# mini_controller_m328.net
KiCad netlist of a schematic drawn in EAGLE
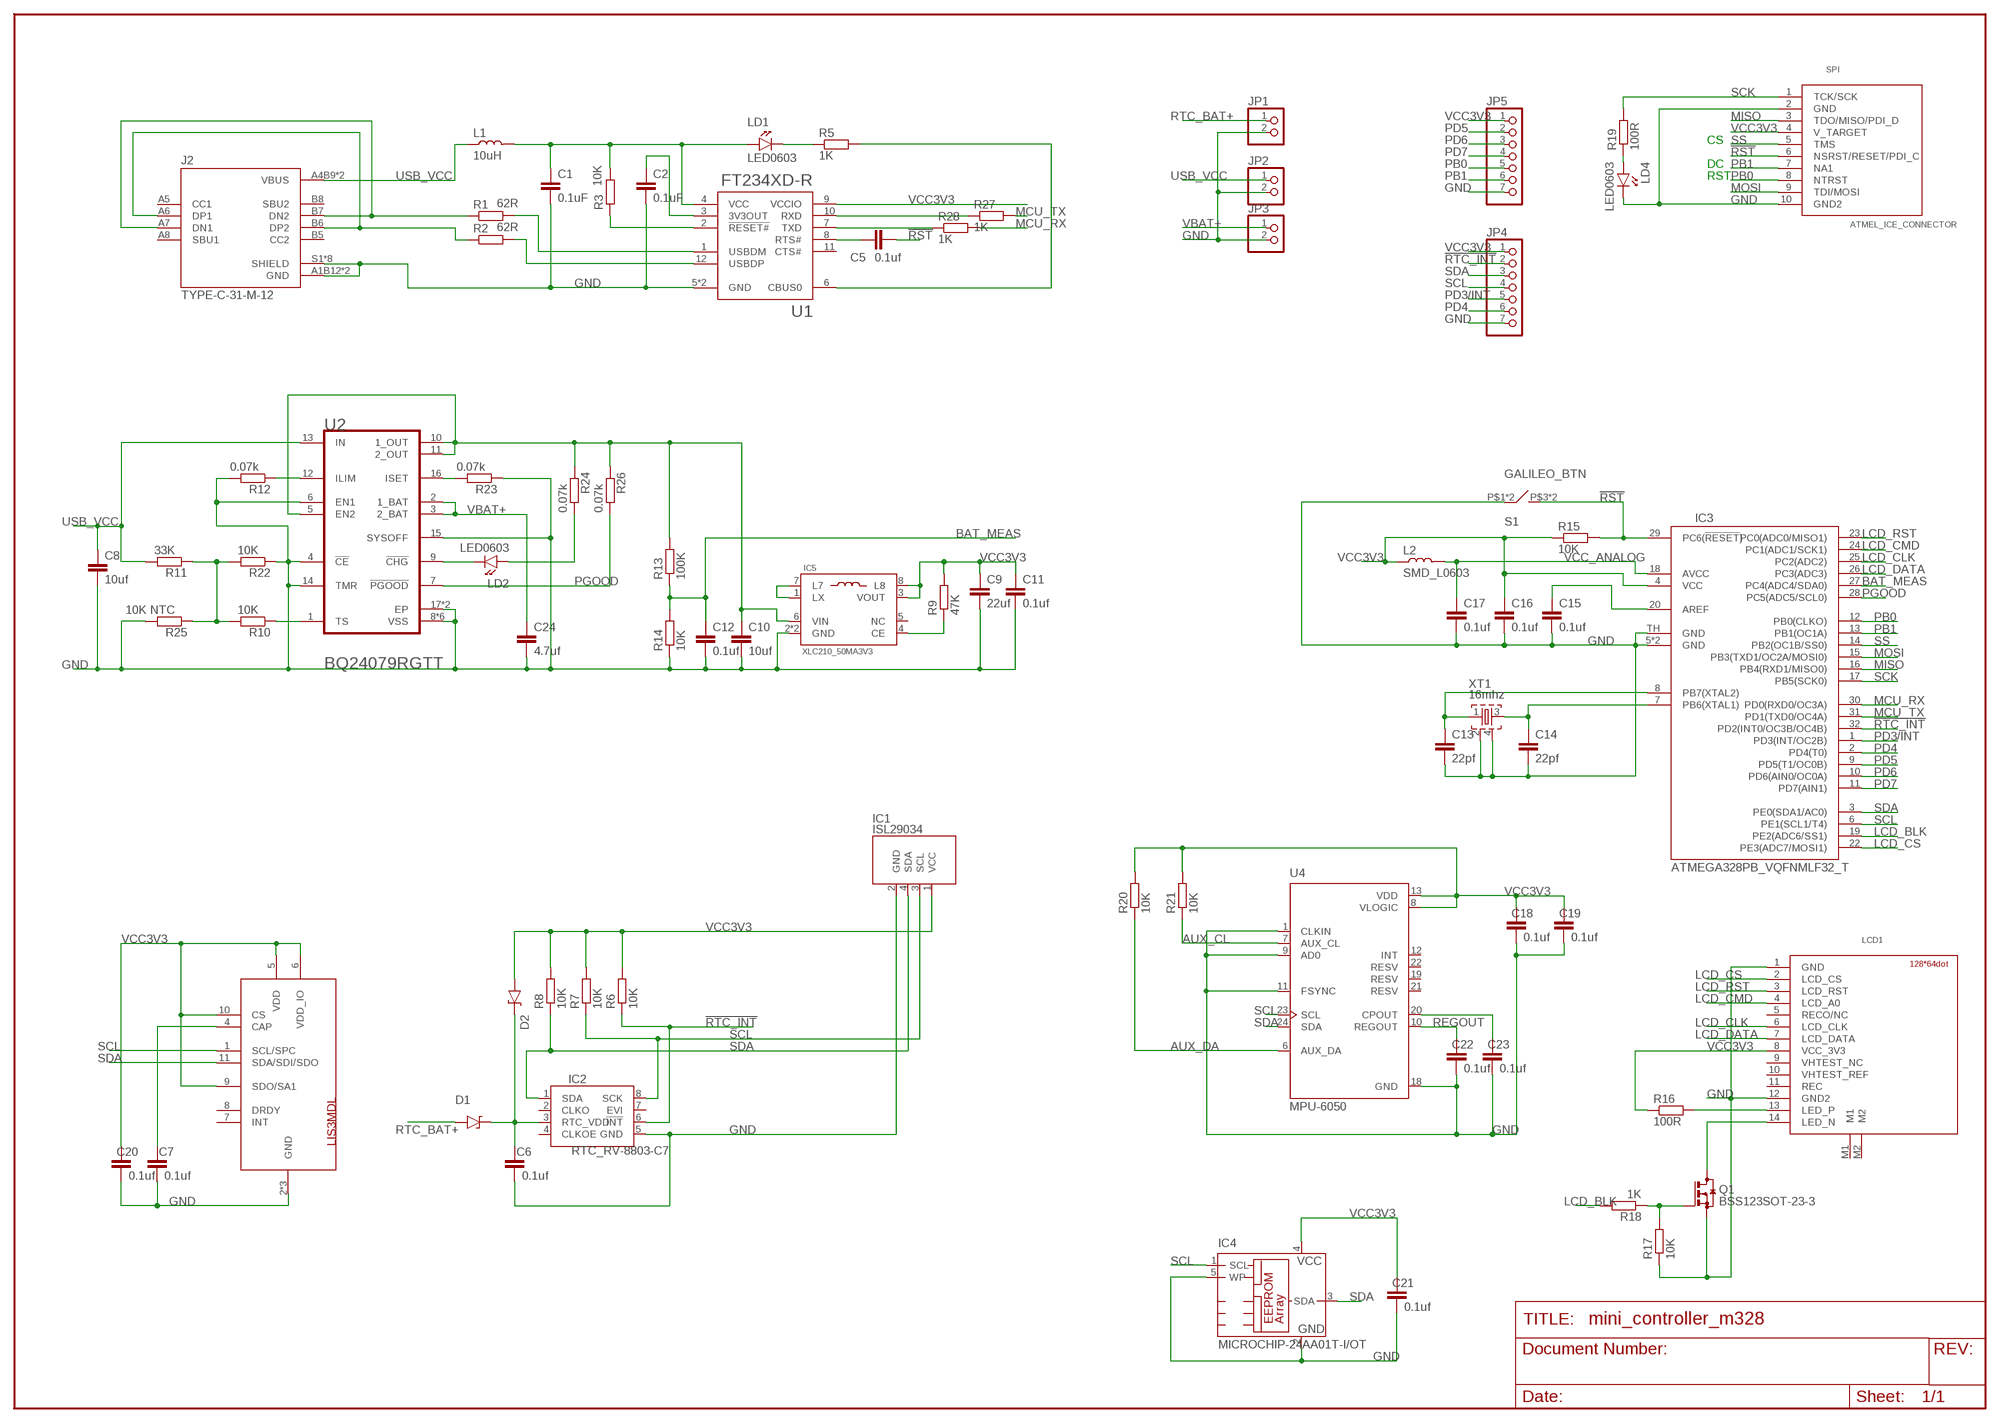
[diagram p0: schematic, sheet 1]

(export (version "E")
  (design (tool "Eeschema 10.0.6"))
  (components
    (comp (ref "C1")
      (value "0.1uF")
      (footprint "eagle-import:0603")
      (libsource (lib "eagle-import") (part "SMD_C0603"))
    )
    (comp (ref "C2")
      (value "0.1uF")
      (footprint "eagle-import:0603")
      (libsource (lib "eagle-import") (part "SMD_C0603"))
    )
    (comp (ref "C5")
      (value "0.1uf")
      (footprint "eagle-import:0603")
      (libsource (lib "eagle-import") (part "SMD_C0603"))
    )
    (comp (ref "C6")
      (value "0.1uf")
      (footprint "eagle-import:0603")
      (libsource (lib "eagle-import") (part "SMD_C0603"))
    )
    (comp (ref "C7")
      (value "0.1uf")
      (footprint "eagle-import:0603")
      (libsource (lib "eagle-import") (part "SMD_C0603"))
    )
    (comp (ref "C8")
      (value "10uf")
      (footprint "eagle-import:1206")
      (libsource (lib "eagle-import") (part "SMD_C1206"))
    )
    (comp (ref "C9")
      (value "22uf")
      (footprint "eagle-import:0805")
      (libsource (lib "eagle-import") (part "SMD_C0805"))
    )
    (comp (ref "C10")
      (value "10uf")
      (footprint "eagle-import:0603")
      (libsource (lib "eagle-import") (part "SMD_C0603"))
    )
    (comp (ref "C11")
      (value "0.1uf")
      (footprint "eagle-import:0603")
      (libsource (lib "eagle-import") (part "SMD_C0603"))
    )
    (comp (ref "C12")
      (value "0.1uf")
      (footprint "eagle-import:0603")
      (libsource (lib "eagle-import") (part "SMD_C0603"))
    )
    (comp (ref "C13")
      (value "22pf")
      (footprint "eagle-import:0603")
      (libsource (lib "eagle-import") (part "SMD_C0603"))
    )
    (comp (ref "C14")
      (value "22pf")
      (footprint "eagle-import:0603")
      (libsource (lib "eagle-import") (part "SMD_C0603"))
    )
    (comp (ref "C15")
      (value "0.1uf")
      (footprint "eagle-import:0603")
      (libsource (lib "eagle-import") (part "SMD_C0603"))
    )
    (comp (ref "C16")
      (value "0.1uf")
      (footprint "eagle-import:0603")
      (libsource (lib "eagle-import") (part "SMD_C0603"))
    )
    (comp (ref "C17")
      (value "0.1uf")
      (footprint "eagle-import:0603")
      (libsource (lib "eagle-import") (part "SMD_C0603"))
    )
    (comp (ref "C18")
      (value "0.1uf")
      (footprint "eagle-import:0603")
      (libsource (lib "eagle-import") (part "SMD_C0603"))
    )
    (comp (ref "C19")
      (value "0.1uf")
      (footprint "eagle-import:0603")
      (libsource (lib "eagle-import") (part "SMD_C0603"))
    )
    (comp (ref "C20")
      (value "0.1uf")
      (footprint "eagle-import:0603")
      (libsource (lib "eagle-import") (part "SMD_C0603"))
    )
    (comp (ref "C21")
      (value "0.1uf")
      (footprint "eagle-import:0603")
      (libsource (lib "eagle-import") (part "SMD_C0603"))
    )
    (comp (ref "C22")
      (value "0.1uf")
      (footprint "eagle-import:0603")
      (libsource (lib "eagle-import") (part "SMD_C0603"))
    )
    (comp (ref "C23")
      (value "0.1uf")
      (footprint "eagle-import:0603")
      (libsource (lib "eagle-import") (part "SMD_C0603"))
    )
    (comp (ref "C24")
      (value "4.7uf")
      (footprint "eagle-import:0805")
      (libsource (lib "eagle-import") (part "SMD_C0805"))
    )
    (comp (ref "D1")
      (value "D_SOD323")
      (footprint "eagle-import:SOD-323_D")
      (libsource (lib "eagle-import") (part "D_SOD323"))
    )
    (comp (ref "D2")
      (value "D_SOD323")
      (footprint "eagle-import:SOD-323_D")
      (libsource (lib "eagle-import") (part "D_SOD323"))
    )
    (comp (ref "IC1")
      (value "ISL29034")
      (footprint "eagle-import:ISL29034")
      (libsource (lib "eagle-import") (part "ISL29034"))
    )
    (comp (ref "IC2")
      (value "RTC_RV-8803-C7")
      (footprint "eagle-import:C7_RTC")
      (libsource (lib "eagle-import") (part "RTC_RV-8803-C7"))
    )
    (comp (ref "IC3")
      (value "ATMEGA328PB_VQFNMLF32_T")
      (footprint "eagle-import:MLF32-TH")
      (libsource (lib "eagle-import") (part "ATMEGA328PB_VQFNMLF32_T"))
    )
    (comp (ref "IC4")
      (value "MICROCHIP-24AA01T-I/OT")
      (footprint "eagle-import:SOT-23(5)")
      (libsource (lib "eagle-import") (part "MICROCHIP-24AA01T-I/OT"))
    )
    (comp (ref "IC5")
      (value "XLC210_50MA3V3")
      (footprint "eagle-import:XCL210_50MA3V3")
      (libsource (lib "eagle-import") (part "XLC210_50MA3V3"))
    )
    (comp (ref "J2")
      (value "TYPE-C-31-M-12")
      (footprint "eagle-import:HRO_TYPE-C-31-M-12")
      (fields (field (name "MF") "HRO Electronics Co., Ltd."))
      (libsource (lib "eagle-import") (part "TYPE-C-31-M-12"))
    )
    (comp (ref "JP1")
      (value "PINHD-1X2")
      (footprint "eagle-import:1X02")
      (libsource (lib "eagle-import") (part "PINHD-1X2"))
    )
    (comp (ref "JP2")
      (value "PINHD-1X2")
      (footprint "eagle-import:1X02")
      (libsource (lib "eagle-import") (part "PINHD-1X2"))
    )
    (comp (ref "JP3")
      (value "PINHD-1X2")
      (footprint "eagle-import:1X02")
      (libsource (lib "eagle-import") (part "PINHD-1X2"))
    )
    (comp (ref "JP4")
      (value "PINHD-1X7")
      (footprint "eagle-import:1X07")
      (libsource (lib "eagle-import") (part "PINHD-1X7"))
    )
    (comp (ref "JP5")
      (value "PINHD-1X7")
      (footprint "eagle-import:1X07")
      (libsource (lib "eagle-import") (part "PINHD-1X7"))
    )
    (comp (ref "L1")
      (value "10uH")
      (footprint "eagle-import:0603")
      (libsource (lib "eagle-import") (part "SMD_L0603"))
    )
    (comp (ref "L2")
      (value "SMD_L0603")
      (footprint "eagle-import:0603")
      (libsource (lib "eagle-import") (part "SMD_L0603"))
    )
    (comp (ref "LCD1")
      (value "ALE_LCD_128X64")
      (footprint "eagle-import:ALE_LCD_14PIN_CONNECTOR")
      (libsource (lib "eagle-import") (part "ALE_LCD_128X64"))
    )
    (comp (ref "LD1")
      (value "LED0603")
      (footprint "eagle-import:0603_P")
      (libsource (lib "eagle-import") (part "LED0603"))
    )
    (comp (ref "LD2")
      (value "LED0603")
      (footprint "eagle-import:0603_P")
      (libsource (lib "eagle-import") (part "LED0603"))
    )
    (comp (ref "LD4")
      (value "LED0603")
      (footprint "eagle-import:0603_P")
      (libsource (lib "eagle-import") (part "LED0603"))
    )
    (comp (ref "Q1")
      (value "BSS123SOT-23-3")
      (footprint "eagle-import:SOT-23(3)")
      (libsource (lib "eagle-import") (part "BSS123SOT-23-3"))
    )
    (comp (ref "R1")
      (value "62R")
      (footprint "eagle-import:0603")
      (libsource (lib "eagle-import") (part "SMD_R0603"))
    )
    (comp (ref "R2")
      (value "62R")
      (footprint "eagle-import:0603")
      (libsource (lib "eagle-import") (part "SMD_R0603"))
    )
    (comp (ref "R3")
      (value "10K")
      (footprint "eagle-import:0603")
      (libsource (lib "eagle-import") (part "SMD_R0603"))
    )
    (comp (ref "R5")
      (value "1K")
      (footprint "eagle-import:0603")
      (libsource (lib "eagle-import") (part "SMD_R0603"))
    )
    (comp (ref "R6")
      (value "10K")
      (footprint "eagle-import:0603")
      (libsource (lib "eagle-import") (part "SMD_R0603"))
    )
    (comp (ref "R7")
      (value "10K")
      (footprint "eagle-import:0603")
      (libsource (lib "eagle-import") (part "SMD_R0603"))
    )
    (comp (ref "R8")
      (value "10K")
      (footprint "eagle-import:0603")
      (libsource (lib "eagle-import") (part "SMD_R0603"))
    )
    (comp (ref "R9")
      (value "47K")
      (footprint "eagle-import:0603")
      (libsource (lib "eagle-import") (part "SMD_R0603"))
    )
    (comp (ref "R10")
      (value "10K")
      (footprint "eagle-import:0603")
      (libsource (lib "eagle-import") (part "SMD_R0603"))
    )
    (comp (ref "R11")
      (value "33K")
      (footprint "eagle-import:0603")
      (libsource (lib "eagle-import") (part "SMD_R0603"))
    )
    (comp (ref "R12")
      (value "0.07k")
      (footprint "eagle-import:0603")
      (libsource (lib "eagle-import") (part "SMD_R0603"))
    )
    (comp (ref "R13")
      (value "100K")
      (footprint "eagle-import:0603")
      (libsource (lib "eagle-import") (part "SMD_R0603"))
    )
    (comp (ref "R14")
      (value "10K")
      (footprint "eagle-import:0603")
      (libsource (lib "eagle-import") (part "SMD_R0603"))
    )
    (comp (ref "R15")
      (value "10K")
      (footprint "eagle-import:0603")
      (libsource (lib "eagle-import") (part "SMD_R0603"))
    )
    (comp (ref "R16")
      (value "100R")
      (footprint "eagle-import:0603")
      (libsource (lib "eagle-import") (part "SMD_R0603"))
    )
    (comp (ref "R17")
      (value "10K")
      (footprint "eagle-import:0603")
      (libsource (lib "eagle-import") (part "SMD_R0603"))
    )
    (comp (ref "R18")
      (value "1K")
      (footprint "eagle-import:0603")
      (libsource (lib "eagle-import") (part "SMD_R0603"))
    )
    (comp (ref "R19")
      (value "100R")
      (footprint "eagle-import:0603")
      (libsource (lib "eagle-import") (part "SMD_R0603"))
    )
    (comp (ref "R20")
      (value "10K")
      (footprint "eagle-import:0603")
      (libsource (lib "eagle-import") (part "SMD_R0603"))
    )
    (comp (ref "R21")
      (value "10K")
      (footprint "eagle-import:0603")
      (libsource (lib "eagle-import") (part "SMD_R0603"))
    )
    (comp (ref "R22")
      (value "10K")
      (footprint "eagle-import:0603")
      (libsource (lib "eagle-import") (part "SMD_R0603"))
    )
    (comp (ref "R23")
      (value "0.07k")
      (footprint "eagle-import:0603")
      (libsource (lib "eagle-import") (part "SMD_R0603"))
    )
    (comp (ref "R24")
      (value "0.07k")
      (footprint "eagle-import:0603")
      (libsource (lib "eagle-import") (part "SMD_R0603"))
    )
    (comp (ref "R25")
      (value "10K NTC")
      (footprint "eagle-import:0603")
      (libsource (lib "eagle-import") (part "SMD_R0603"))
    )
    (comp (ref "R26")
      (value "0.07k")
      (footprint "eagle-import:0603")
      (libsource (lib "eagle-import") (part "SMD_R0603"))
    )
    (comp (ref "R27")
      (value "1K")
      (footprint "eagle-import:0603")
      (libsource (lib "eagle-import") (part "SMD_R0603"))
    )
    (comp (ref "R28")
      (value "1K")
      (footprint "eagle-import:0603")
      (libsource (lib "eagle-import") (part "SMD_R0603"))
    )
    (comp (ref "S1")
      (value "GALILEO_BTN")
      (footprint "eagle-import:GALILEO_VERT_BTN")
      (libsource (lib "eagle-import") (part "GALILEO_BTN"))
    )
    (comp (ref "SPI")
      (value "ATMEL_ICE_CONNECTOR")
      (footprint "eagle-import:MINI10P_SPI_JTAG_PDI")
      (libsource (lib "eagle-import") (part "ATMEL_ICE_CONNECTOR"))
    )
    (comp (ref "U$1")
      (value "LIS3MDL")
      (footprint "eagle-import:LGA-12")
      (fields (field (name "MF") "STMicroelectronics"))
      (libsource (lib "eagle-import") (part "LIS3MDL"))
    )
    (comp (ref "U1")
      (value "FT234XD-R")
      (footprint "eagle-import:IC_FT234XD-R")
      (fields (field (name "MF") "FTDI,"))
      (libsource (lib "eagle-import") (part "FT234XD-R"))
    )
    (comp (ref "U2")
      (value "TEXAS_INSTRUMENTS_BQ24079RGTTTEXAS_INSTRUMENTS_BQ24079RGTT_0_0")
      (footprint "eagle-import:TEXAS_INSTRUMENTS_BQ24079RGTT_0")
      (fields (field (name "MF") "Texas Instruments") (field (name "MPN") "BQ24079RGTT"))
      (libsource (lib "eagle-import") (part "TEXAS_INSTRUMENTS_BQ24079RGTTTEXAS_INSTRUMENTS_BQ24079RGTT_0_0"))
    )
    (comp (ref "U4")
      (value "MPU-6050")
      (footprint "eagle-import:QFN50P400X400X95-24N")
      (fields (field (name "MF") "TDK InvenSense"))
      (libsource (lib "eagle-import") (part "MPU-6050"))
    )
    (comp (ref "XT1")
      (value "16mhz")
      (footprint "eagle-import:QUARTZ_3X3MM")
      (libsource (lib "eagle-import") (part "QUARTZ_ZQ"))
    )
  )
  (nets
    (net (code "1") (name "/AUX_CL") (class "Default")
      (node (ref "R21") (pin "1") (pinfunction "1_1") (pintype "passive"))
      (node (ref "U4") (pin "7") (pinfunction "AUX_CL_7") (pintype "input"))
    )
    (net (code "2") (name "/AUX_DA") (class "Default")
      (node (ref "R20") (pin "1") (pinfunction "1_1") (pintype "passive"))
      (node (ref "U4") (pin "6") (pinfunction "AUX_DA_6") (pintype "bidirectional"))
    )
    (net (code "3") (name "/BAT_MEAS") (class "Default")
      (node (ref "C12") (pin "1") (pinfunction "1_1") (pintype "passive"))
      (node (ref "IC3") (pin "27") (pinfunction "PC4(ADC4/SDA0)_27") (pintype "bidirectional"))
      (node (ref "R13") (pin "1") (pinfunction "1_1") (pintype "passive"))
      (node (ref "R14") (pin "2") (pinfunction "2_2") (pintype "passive"))
    )
    (net (code "4") (name "/GND") (class "Default")
      (node (ref "C1") (pin "2") (pinfunction "2_2") (pintype "passive"))
      (node (ref "C10") (pin "2") (pinfunction "2_2") (pintype "passive"))
      (node (ref "C11") (pin "2") (pinfunction "2_2") (pintype "passive"))
      (node (ref "C12") (pin "2") (pinfunction "2_2") (pintype "passive"))
      (node (ref "C13") (pin "2") (pinfunction "2_2") (pintype "passive"))
      (node (ref "C14") (pin "2") (pinfunction "2_2") (pintype "passive"))
      (node (ref "C15") (pin "2") (pinfunction "2_2") (pintype "passive"))
      (node (ref "C16") (pin "2") (pinfunction "2_2") (pintype "passive"))
      (node (ref "C17") (pin "2") (pinfunction "2_2") (pintype "passive"))
      (node (ref "C18") (pin "2") (pinfunction "2_2") (pintype "passive"))
      (node (ref "C19") (pin "2") (pinfunction "2_2") (pintype "passive"))
      (node (ref "C2") (pin "2") (pinfunction "2_2") (pintype "passive"))
      (node (ref "C20") (pin "2") (pinfunction "2_2") (pintype "passive"))
      (node (ref "C21") (pin "2") (pinfunction "2_2") (pintype "passive"))
      (node (ref "C22") (pin "2") (pinfunction "2_2") (pintype "passive"))
      (node (ref "C23") (pin "2") (pinfunction "2_2") (pintype "passive"))
      (node (ref "C24") (pin "2") (pinfunction "2_2") (pintype "passive"))
      (node (ref "C6") (pin "2") (pinfunction "2_2") (pintype "passive"))
      (node (ref "C7") (pin "2") (pinfunction "2_2") (pintype "passive"))
      (node (ref "C8") (pin "2") (pinfunction "2_2") (pintype "passive"))
      (node (ref "C9") (pin "2") (pinfunction "2_2") (pintype "passive"))
      (node (ref "IC1") (pin "2") (pinfunction "GND_2") (pintype "bidirectional"))
      (node (ref "IC2") (pin "5") (pinfunction "GND_5") (pintype "bidirectional"))
      (node (ref "IC3") (pin "21") (pinfunction "GND_21") (pintype "power_in"))
      (node (ref "IC3") (pin "5") (pinfunction "GND_5") (pintype "power_in"))
      (node (ref "IC3") (pin "TH") (pinfunction "GND_TH") (pintype "power_in"))
      (node (ref "IC4") (pin "2") (pinfunction "GND_2") (pintype "power_in"))
      (node (ref "IC4") (pin "5") (pinfunction "WP_5") (pintype "input"))
      (node (ref "IC5") (pin "2") (pinfunction "GND_2") (pintype "bidirectional"))
      (node (ref "IC5") (pin "9") (pinfunction "GND_9") (pintype "bidirectional"))
      (node (ref "J2") (pin "A1B12") (pinfunction "GND_A1B12") (pintype "power_in"))
      (node (ref "J2") (pin "B1A12") (pinfunction "GND_B1A12") (pintype "power_in"))
      (node (ref "J2") (pin "S1") (pinfunction "SHIELD_S1") (pintype "passive"))
      (node (ref "J2") (pin "S2") (pinfunction "SHIELD_S2") (pintype "passive"))
      (node (ref "J2") (pin "S3") (pinfunction "SHIELD_S3") (pintype "passive"))
      (node (ref "J2") (pin "S4") (pinfunction "SHIELD_S4") (pintype "passive"))
      (node (ref "J2") (pin "S5") (pinfunction "SHIELD_S5") (pintype "passive"))
      (node (ref "J2") (pin "S6") (pinfunction "SHIELD_S6") (pintype "passive"))
      (node (ref "J2") (pin "S7") (pinfunction "SHIELD_S7") (pintype "passive"))
      (node (ref "J2") (pin "S8") (pinfunction "SHIELD_S8") (pintype "passive"))
      (node (ref "JP1") (pin "2") (pinfunction "2_2") (pintype "passive"))
      (node (ref "JP2") (pin "2") (pinfunction "2_2") (pintype "passive"))
      (node (ref "JP3") (pin "2") (pinfunction "2_2") (pintype "passive"))
      (node (ref "JP4") (pin "7") (pinfunction "7_7") (pintype "passive"))
      (node (ref "JP5") (pin "7") (pinfunction "7_7") (pintype "passive"))
      (node (ref "LCD1") (pin "1") (pinfunction "GND_1") (pintype "bidirectional"))
      (node (ref "LCD1") (pin "12") (pinfunction "GND2_12") (pintype "bidirectional"))
      (node (ref "LD4") (pin "1") (pinfunction "K_1") (pintype "bidirectional"))
      (node (ref "Q1") (pin "2") (pinfunction "S_2") (pintype "passive"))
      (node (ref "R12") (pin "2") (pinfunction "2_2") (pintype "passive"))
      (node (ref "R14") (pin "1") (pinfunction "1_1") (pintype "passive"))
      (node (ref "R17") (pin "1") (pinfunction "1_1") (pintype "passive"))
      (node (ref "R22") (pin "1") (pinfunction "1_1") (pintype "passive"))
      (node (ref "R23") (pin "1") (pinfunction "1_1") (pintype "passive"))
      (node (ref "R25") (pin "2") (pinfunction "2_2") (pintype "passive"))
      (node (ref "S1") (pin "P$1") (pinfunction "1_P$1") (pintype "bidirectional"))
      (node (ref "S1") (pin "P$2") (pinfunction "1_P$2") (pintype "bidirectional"))
      (node (ref "SPI") (pin "10") (pinfunction "GND2_10") (pintype "bidirectional"))
      (node (ref "SPI") (pin "2") (pinfunction "GND_2") (pintype "bidirectional"))
      (node (ref "U$1") (pin "12") (pinfunction "GND_12") (pintype "bidirectional"))
      (node (ref "U$1") (pin "2") (pinfunction "GND_2") (pintype "bidirectional"))
      (node (ref "U$1") (pin "3") (pinfunction "GND_3") (pintype "bidirectional"))
      (node (ref "U1") (pin "13") (pinfunction "GND_13") (pintype "power_in"))
      (node (ref "U1") (pin "5") (pinfunction "GND_5") (pintype "power_in"))
      (node (ref "U2") (pin "14") (pinfunction "TMR_14") (pintype "passive"))
      (node (ref "U2") (pin "15") (pinfunction "SYSOFF_15") (pintype "input"))
      (node (ref "U2") (pin "17") (pinfunction "EP_17") (pintype "power_in"))
      (node (ref "U2") (pin "17-2") (pinfunction "EP_17-2") (pintype "power_in"))
      (node (ref "U2") (pin "4") (pinfunction "~{CE}_4") (pintype "input"))
      (node (ref "U2") (pin "6") (pinfunction "EN1_6") (pintype "input"))
      (node (ref "U2") (pin "8") (pinfunction "VSS_8") (pintype "power_in"))
      (node (ref "U2") (pin "PAD_1") (pinfunction "VSS_PAD_1") (pintype "power_in"))
      (node (ref "U2") (pin "PAD_2") (pinfunction "VSS_PAD_2") (pintype "power_in"))
      (node (ref "U2") (pin "PAD_3") (pinfunction "VSS_PAD_3") (pintype "power_in"))
      (node (ref "U2") (pin "PAD_4") (pinfunction "VSS_PAD_4") (pintype "power_in"))
      (node (ref "U2") (pin "PAD_5") (pinfunction "VSS_PAD_5") (pintype "power_in"))
      (node (ref "U4") (pin "1") (pinfunction "CLKIN_1") (pintype "input"))
      (node (ref "U4") (pin "11") (pinfunction "FSYNC_11") (pintype "input"))
      (node (ref "U4") (pin "18") (pinfunction "GND_18") (pintype "power_in"))
      (node (ref "U4") (pin "9") (pinfunction "AD0_9") (pintype "input"))
      (node (ref "XT1") (pin "2") (pinfunction "2_2") (pintype "passive"))
      (node (ref "XT1") (pin "4") (pinfunction "4_4") (pintype "passive"))
    )
    (net (code "5") (name "/LCD_BLK") (class "Default")
      (node (ref "IC3") (pin "19") (pinfunction "PE2(ADC6/SS1)_19") (pintype "bidirectional"))
      (node (ref "R18") (pin "2") (pinfunction "2_2") (pintype "passive"))
    )
    (net (code "6") (name "/LCD_CLK") (class "Default")
      (node (ref "IC3") (pin "25") (pinfunction "PC2(ADC2)_25") (pintype "bidirectional"))
      (node (ref "LCD1") (pin "6") (pinfunction "LCD_CLK_6") (pintype "bidirectional"))
    )
    (net (code "7") (name "/LCD_CMD") (class "Default")
      (node (ref "IC3") (pin "24") (pinfunction "PC1(ADC1/SCK1)_24") (pintype "bidirectional"))
      (node (ref "LCD1") (pin "4") (pinfunction "LCD_A0_4") (pintype "bidirectional"))
    )
    (net (code "8") (name "/LCD_CS") (class "Default")
      (node (ref "IC3") (pin "22") (pinfunction "PE3(ADC7/MOSI1)_22") (pintype "bidirectional"))
      (node (ref "LCD1") (pin "2") (pinfunction "LCD_CS_2") (pintype "bidirectional"))
    )
    (net (code "9") (name "/LCD_DATA") (class "Default")
      (node (ref "IC3") (pin "26") (pinfunction "PC3(ADC3)_26") (pintype "bidirectional"))
      (node (ref "LCD1") (pin "7") (pinfunction "LCD_DATA_7") (pintype "bidirectional"))
    )
    (net (code "10") (name "/LCD_RST") (class "Default")
      (node (ref "IC3") (pin "23") (pinfunction "PC0(ADC0/MISO1)_23") (pintype "bidirectional"))
      (node (ref "LCD1") (pin "3") (pinfunction "LCD_RST_3") (pintype "bidirectional"))
    )
    (net (code "11") (name "/MCU_RX") (class "Default")
      (node (ref "IC3") (pin "30") (pinfunction "PD0(RXD0/OC3A)_30") (pintype "bidirectional"))
      (node (ref "R28") (pin "2") (pinfunction "2_2") (pintype "passive"))
    )
    (net (code "12") (name "/MCU_TX") (class "Default")
      (node (ref "IC3") (pin "31") (pinfunction "PD1(TXD0/OC4A)_31") (pintype "bidirectional"))
      (node (ref "R27") (pin "2") (pinfunction "2_2") (pintype "passive"))
    )
    (net (code "13") (name "/MISO") (class "Default")
      (node (ref "IC3") (pin "16") (pinfunction "PB4(RXD1/MISO0)_16") (pintype "bidirectional"))
      (node (ref "SPI") (pin "3") (pinfunction "TDO/MISO/PDI_D_3") (pintype "bidirectional"))
    )
    (net (code "14") (name "/MOSI") (class "Default")
      (node (ref "IC3") (pin "15") (pinfunction "PB3(TXD1/OC2A/MOSI0)_15") (pintype "bidirectional"))
      (node (ref "SPI") (pin "9") (pinfunction "TDI/MOSI_9") (pintype "bidirectional"))
    )
    (net (code "15") (name "/PB0") (class "Default")
      (node (ref "IC3") (pin "12") (pinfunction "PB0(CLKO)_12") (pintype "bidirectional"))
      (node (ref "JP5") (pin "5") (pinfunction "5_5") (pintype "passive"))
      (node (ref "SPI") (pin "8") (pinfunction "NTRST_8") (pintype "bidirectional"))
    )
    (net (code "16") (name "/PB1") (class "Default")
      (node (ref "IC3") (pin "13") (pinfunction "PB1(OC1A)_13") (pintype "bidirectional"))
      (node (ref "JP5") (pin "6") (pinfunction "6_6") (pintype "passive"))
      (node (ref "SPI") (pin "7") (pinfunction "NA1_7") (pintype "bidirectional"))
    )
    (net (code "17") (name "/PD3{slash}INT") (class "Default")
      (node (ref "IC3") (pin "1") (pinfunction "PD3(INT/OC2B)_1") (pintype "bidirectional"))
      (node (ref "JP4") (pin "5") (pinfunction "5_5") (pintype "passive"))
    )
    (net (code "18") (name "/PD4") (class "Default")
      (node (ref "IC3") (pin "2") (pinfunction "PD4(T0)_2") (pintype "bidirectional"))
      (node (ref "JP4") (pin "6") (pinfunction "6_6") (pintype "passive"))
    )
    (net (code "19") (name "/PD5") (class "Default")
      (node (ref "IC3") (pin "9") (pinfunction "PD5(T1/OC0B)_9") (pintype "bidirectional"))
      (node (ref "JP5") (pin "2") (pinfunction "2_2") (pintype "passive"))
    )
    (net (code "20") (name "/PD6") (class "Default")
      (node (ref "IC3") (pin "10") (pinfunction "PD6(AIN0/OC0A)_10") (pintype "bidirectional"))
      (node (ref "JP5") (pin "3") (pinfunction "3_3") (pintype "passive"))
    )
    (net (code "21") (name "/PD7") (class "Default")
      (node (ref "IC3") (pin "11") (pinfunction "PD7(AIN1)_11") (pintype "bidirectional"))
      (node (ref "JP5") (pin "4") (pinfunction "4_4") (pintype "passive"))
    )
    (net (code "22") (name "/PGOOD") (class "Default")
      (node (ref "IC3") (pin "28") (pinfunction "PC5(ADC5/SCL0)_28") (pintype "bidirectional"))
      (node (ref "R26") (pin "2") (pinfunction "2_2") (pintype "passive"))
      (node (ref "U2") (pin "7") (pinfunction "~{PGOOD}_7") (pintype "tri_state"))
    )
    (net (code "23") (name "/REGOUT") (class "Default")
      (node (ref "C22") (pin "1") (pinfunction "1_1") (pintype "passive"))
      (node (ref "U4") (pin "10") (pinfunction "REGOUT_10") (pintype "passive"))
    )
    (net (code "24") (name "/RTC_BAT+") (class "Default")
      (node (ref "D1") (pin "A") (pinfunction "A_A") (pintype "bidirectional"))
      (node (ref "JP1") (pin "1") (pinfunction "1_1") (pintype "passive"))
    )
    (net (code "25") (name "/SCK") (class "Default")
      (node (ref "IC3") (pin "17") (pinfunction "PB5(SCK0)_17") (pintype "bidirectional"))
      (node (ref "R19") (pin "2") (pinfunction "2_2") (pintype "passive"))
      (node (ref "SPI") (pin "1") (pinfunction "TCK/SCK_1") (pintype "bidirectional"))
    )
    (net (code "26") (name "/SCL") (class "Default")
      (node (ref "IC1") (pin "3") (pinfunction "SCL_3") (pintype "bidirectional"))
      (node (ref "IC2") (pin "8") (pinfunction "SCK_8") (pintype "bidirectional"))
      (node (ref "IC3") (pin "6") (pinfunction "PE1(SCL1/T4)_6") (pintype "bidirectional"))
      (node (ref "IC4") (pin "1") (pinfunction "SCL_1") (pintype "input"))
      (node (ref "JP4") (pin "4") (pinfunction "4_4") (pintype "passive"))
      (node (ref "R7") (pin "1") (pinfunction "1_1") (pintype "passive"))
      (node (ref "U$1") (pin "1") (pinfunction "SCL/SPC_1") (pintype "bidirectional"))
      (node (ref "U4") (pin "23") (pinfunction "SCL_23") (pintype "input"))
    )
    (net (code "27") (name "/SDA") (class "Default")
      (node (ref "IC1") (pin "4") (pinfunction "SDA_4") (pintype "bidirectional"))
      (node (ref "IC2") (pin "1") (pinfunction "SDA_1") (pintype "bidirectional"))
      (node (ref "IC3") (pin "3") (pinfunction "PE0(SDA1/AC0)_3") (pintype "bidirectional"))
      (node (ref "IC4") (pin "3") (pinfunction "SDA_3") (pintype "bidirectional"))
      (node (ref "JP4") (pin "3") (pinfunction "3_3") (pintype "passive"))
      (node (ref "R8") (pin "1") (pinfunction "1_1") (pintype "passive"))
      (node (ref "U$1") (pin "11") (pinfunction "SDA/SDI/SDO_11") (pintype "bidirectional"))
      (node (ref "U4") (pin "24") (pinfunction "SDA_24") (pintype "bidirectional"))
    )
    (net (code "28") (name "/SS") (class "Default")
      (node (ref "IC3") (pin "14") (pinfunction "PB2(OC1B/SS0)_14") (pintype "bidirectional"))
      (node (ref "SPI") (pin "5") (pinfunction "TMS_5") (pintype "bidirectional"))
    )
    (net (code "29") (name "/USB_VCC") (class "Default")
      (node (ref "C8") (pin "1") (pinfunction "1_1") (pintype "passive"))
      (node (ref "J2") (pin "A4B9") (pinfunction "VBUS_A4B9") (pintype "power_in"))
      (node (ref "J2") (pin "B4A9") (pinfunction "VBUS_B4A9") (pintype "power_in"))
      (node (ref "JP2") (pin "1") (pinfunction "1_1") (pintype "passive"))
      (node (ref "L1") (pin "1") (pinfunction "1_1") (pintype "passive"))
      (node (ref "R11") (pin "2") (pinfunction "2_2") (pintype "passive"))
      (node (ref "U2") (pin "13") (pinfunction "IN_13") (pintype "power_in"))
    )
    (net (code "30") (name "/VBAT+") (class "Default")
      (node (ref "C24") (pin "1") (pinfunction "1_1") (pintype "passive"))
      (node (ref "JP3") (pin "1") (pinfunction "1_1") (pintype "passive"))
      (node (ref "U2") (pin "2") (pinfunction "1_BAT_2") (pintype "power_in"))
      (node (ref "U2") (pin "3") (pinfunction "2_BAT_3") (pintype "power_in"))
    )
    (net (code "31") (name "/VCC3V3") (class "Default")
      (node (ref "C11") (pin "1") (pinfunction "1_1") (pintype "passive"))
      (node (ref "C16") (pin "1") (pinfunction "1_1") (pintype "passive"))
      (node (ref "C18") (pin "1") (pinfunction "1_1") (pintype "passive"))
      (node (ref "C19") (pin "1") (pinfunction "1_1") (pintype "passive"))
      (node (ref "C20") (pin "1") (pinfunction "1_1") (pintype "passive"))
      (node (ref "C21") (pin "1") (pinfunction "1_1") (pintype "passive"))
      (node (ref "C9") (pin "1") (pinfunction "1_1") (pintype "passive"))
      (node (ref "D2") (pin "A") (pinfunction "A_A") (pintype "bidirectional"))
      (node (ref "IC1") (pin "1") (pinfunction "VCC_1") (pintype "bidirectional"))
      (node (ref "IC3") (pin "4") (pinfunction "VCC_4") (pintype "power_in"))
      (node (ref "IC4") (pin "4") (pinfunction "VCC_4") (pintype "power_in"))
      (node (ref "IC5") (pin "3") (pinfunction "VOUT_3") (pintype "bidirectional"))
      (node (ref "IC5") (pin "8") (pinfunction "L8_8") (pintype "bidirectional"))
      (node (ref "JP4") (pin "1") (pinfunction "1_1") (pintype "passive"))
      (node (ref "JP5") (pin "1") (pinfunction "1_1") (pintype "passive"))
      (node (ref "L2") (pin "1") (pinfunction "1_1") (pintype "passive"))
      (node (ref "LCD1") (pin "8") (pinfunction "VCC_3V3_8") (pintype "bidirectional"))
      (node (ref "R15") (pin "1") (pinfunction "1_1") (pintype "passive"))
      (node (ref "R16") (pin "1") (pinfunction "1_1") (pintype "passive"))
      (node (ref "R20") (pin "2") (pinfunction "2_2") (pintype "passive"))
      (node (ref "R21") (pin "2") (pinfunction "2_2") (pintype "passive"))
      (node (ref "R6") (pin "2") (pinfunction "2_2") (pintype "passive"))
      (node (ref "R7") (pin "2") (pinfunction "2_2") (pintype "passive"))
      (node (ref "R8") (pin "2") (pinfunction "2_2") (pintype "passive"))
      (node (ref "R9") (pin "2") (pinfunction "2_2") (pintype "passive"))
      (node (ref "SPI") (pin "4") (pinfunction "V_TARGET_4") (pintype "bidirectional"))
      (node (ref "U$1") (pin "10") (pinfunction "CS_10") (pintype "bidirectional"))
      (node (ref "U$1") (pin "5") (pinfunction "VDD_5") (pintype "bidirectional"))
      (node (ref "U$1") (pin "6") (pinfunction "VDD_IO_6") (pintype "bidirectional"))
      (node (ref "U$1") (pin "9") (pinfunction "SDO/SA1_9") (pintype "bidirectional"))
      (node (ref "U1") (pin "9") (pinfunction "VCCIO_9") (pintype "power_in"))
      (node (ref "U4") (pin "13") (pinfunction "VDD_13") (pintype "power_in"))
      (node (ref "U4") (pin "8") (pinfunction "VLOGIC_8") (pintype "power_in"))
    )
    (net (code "32") (name "/VCC_ANALOG") (class "Default")
      (node (ref "C17") (pin "1") (pinfunction "1_1") (pintype "passive"))
      (node (ref "IC3") (pin "18") (pinfunction "AVCC_18") (pintype "power_in"))
      (node (ref "L2") (pin "2") (pinfunction "2_2") (pintype "passive"))
    )
    (net (code "33") (name "/~{RST}") (class "Default")
      (node (ref "C5") (pin "2") (pinfunction "2_2") (pintype "passive"))
      (node (ref "IC3") (pin "29") (pinfunction "PC6(~{RESET})_29") (pintype "bidirectional"))
      (node (ref "R15") (pin "2") (pinfunction "2_2") (pintype "passive"))
      (node (ref "S1") (pin "P$3") (pinfunction "4_P$3") (pintype "bidirectional"))
      (node (ref "S1") (pin "P$4") (pinfunction "4_P$4") (pintype "bidirectional"))
      (node (ref "SPI") (pin "6") (pinfunction "NSRST/RESET/PDI_C_6") (pintype "bidirectional"))
    )
    (net (code "34") (name "/~{RTC_INT}") (class "Default")
      (node (ref "IC2") (pin "6") (pinfunction "~{INT}_6") (pintype "bidirectional"))
      (node (ref "IC3") (pin "32") (pinfunction "PD2(INT0/OC3B/OC4B)_32") (pintype "bidirectional"))
      (node (ref "JP4") (pin "2") (pinfunction "2_2") (pintype "passive"))
      (node (ref "R6") (pin "1") (pinfunction "1_1") (pintype "passive"))
    )
    (net (code "35") (name "Net-(IC2-RTC_VDD)") (class "Default")
      (node (ref "C6") (pin "1") (pinfunction "1_1") (pintype "passive"))
      (node (ref "D1") (pin "K") (pinfunction "K_K") (pintype "bidirectional"))
      (node (ref "D2") (pin "K") (pinfunction "K_K") (pintype "bidirectional"))
      (node (ref "IC2") (pin "3") (pinfunction "RTC_VDD_3") (pintype "bidirectional"))
    )
    (net (code "36") (name "Net-(IC3-AREF)") (class "Default")
      (node (ref "C15") (pin "1") (pinfunction "1_1") (pintype "passive"))
      (node (ref "IC3") (pin "20") (pinfunction "AREF_20") (pintype "passive"))
    )
    (net (code "37") (name "Net-(IC3-PB6(XTAL1))") (class "Default")
      (node (ref "C14") (pin "1") (pinfunction "1_1") (pintype "passive"))
      (node (ref "IC3") (pin "7") (pinfunction "PB6(XTAL1)_7") (pintype "bidirectional"))
      (node (ref "XT1") (pin "3") (pinfunction "3_3") (pintype "passive"))
    )
    (net (code "38") (name "Net-(IC3-PB7(XTAL2))") (class "Default")
      (node (ref "C13") (pin "1") (pinfunction "1_1") (pintype "passive"))
      (node (ref "IC3") (pin "8") (pinfunction "PB7(XTAL2)_8") (pintype "bidirectional"))
      (node (ref "XT1") (pin "1") (pinfunction "1_1") (pintype "passive"))
    )
    (net (code "39") (name "Net-(IC5-CE)") (class "Default")
      (node (ref "IC5") (pin "4") (pinfunction "CE_4") (pintype "bidirectional"))
      (node (ref "R9") (pin "1") (pinfunction "1_1") (pintype "passive"))
    )
    (net (code "40") (name "Net-(IC5-L7)") (class "Default")
      (node (ref "IC5") (pin "1") (pinfunction "LX_1") (pintype "bidirectional"))
      (node (ref "IC5") (pin "7") (pinfunction "L7_7") (pintype "bidirectional"))
    )
    (net (code "41") (name "Net-(IC5-VIN)") (class "Default")
      (node (ref "C10") (pin "1") (pinfunction "1_1") (pintype "passive"))
      (node (ref "IC5") (pin "6") (pinfunction "VIN_6") (pintype "bidirectional"))
      (node (ref "R13") (pin "2") (pinfunction "2_2") (pintype "passive"))
      (node (ref "R24") (pin "1") (pinfunction "1_1") (pintype "passive"))
      (node (ref "R26") (pin "1") (pinfunction "1_1") (pintype "passive"))
      (node (ref "U2") (pin "10") (pinfunction "1_OUT_10") (pintype "power_in"))
      (node (ref "U2") (pin "11") (pinfunction "2_OUT_11") (pintype "power_in"))
      (node (ref "U2") (pin "5") (pinfunction "EN2_5") (pintype "input"))
    )
    (net (code "42") (name "Net-(J2-DN1)") (class "Default")
      (node (ref "J2") (pin "A7") (pinfunction "DN1_A7") (pintype "bidirectional"))
      (node (ref "J2") (pin "B7") (pinfunction "DN2_B7") (pintype "bidirectional"))
      (node (ref "R1") (pin "1") (pinfunction "1_1") (pintype "passive"))
    )
    (net (code "43") (name "Net-(J2-DP1)") (class "Default")
      (node (ref "J2") (pin "A6") (pinfunction "DP1_A6") (pintype "bidirectional"))
      (node (ref "J2") (pin "B6") (pinfunction "DP2_B6") (pintype "bidirectional"))
      (node (ref "R2") (pin "1") (pinfunction "1_1") (pintype "passive"))
    )
    (net (code "44") (name "Net-(LCD1-LED_N)") (class "Default")
      (node (ref "LCD1") (pin "14") (pinfunction "LED_N_14") (pintype "bidirectional"))
      (node (ref "Q1") (pin "3") (pinfunction "D_3") (pintype "passive"))
    )
    (net (code "45") (name "Net-(LCD1-LED_P)") (class "Default")
      (node (ref "LCD1") (pin "13") (pinfunction "LED_P_13") (pintype "bidirectional"))
      (node (ref "R16") (pin "2") (pinfunction "2_2") (pintype "passive"))
    )
    (net (code "46") (name "Net-(LD1-A)") (class "Default")
      (node (ref "C1") (pin "1") (pinfunction "1_1") (pintype "passive"))
      (node (ref "L1") (pin "2") (pinfunction "2_2") (pintype "passive"))
      (node (ref "LD1") (pin "2") (pinfunction "A_2") (pintype "bidirectional"))
      (node (ref "R3") (pin "2") (pinfunction "2_2") (pintype "passive"))
      (node (ref "U1") (pin "4") (pinfunction "VCC_4") (pintype "power_in"))
    )
    (net (code "47") (name "Net-(LD1-K)") (class "Default")
      (node (ref "LD1") (pin "1") (pinfunction "K_1") (pintype "bidirectional"))
      (node (ref "R5") (pin "1") (pinfunction "1_1") (pintype "passive"))
    )
    (net (code "48") (name "Net-(LD2-A)") (class "Default")
      (node (ref "LD2") (pin "2") (pinfunction "A_2") (pintype "bidirectional"))
      (node (ref "R24") (pin "2") (pinfunction "2_2") (pintype "passive"))
    )
    (net (code "49") (name "Net-(LD2-K)") (class "Default")
      (node (ref "LD2") (pin "1") (pinfunction "K_1") (pintype "bidirectional"))
      (node (ref "U2") (pin "9") (pinfunction "~{CHG}_9") (pintype "tri_state"))
    )
    (net (code "50") (name "Net-(LD4-A)") (class "Default")
      (node (ref "LD4") (pin "2") (pinfunction "A_2") (pintype "bidirectional"))
      (node (ref "R19") (pin "1") (pinfunction "1_1") (pintype "passive"))
    )
    (net (code "51") (name "Net-(Q1-G)") (class "Default")
      (node (ref "Q1") (pin "1") (pinfunction "G_1") (pintype "passive"))
      (node (ref "R17") (pin "2") (pinfunction "2_2") (pintype "passive"))
      (node (ref "R18") (pin "1") (pinfunction "1_1") (pintype "passive"))
    )
    (net (code "52") (name "Net-(R10-Pad2)") (class "Default")
      (node (ref "R10") (pin "2") (pinfunction "2_2") (pintype "passive"))
      (node (ref "R11") (pin "1") (pinfunction "1_1") (pintype "passive"))
      (node (ref "R22") (pin "2") (pinfunction "2_2") (pintype "passive"))
      (node (ref "R25") (pin "1") (pinfunction "1_1") (pintype "passive"))
    )
    (net (code "53") (name "Net-(U$1-CAP)") (class "Default")
      (node (ref "C7") (pin "1") (pinfunction "1_1") (pintype "passive"))
      (node (ref "U$1") (pin "4") (pinfunction "CAP_4") (pintype "bidirectional"))
    )
    (net (code "54") (name "Net-(U1-3V3OUT)") (class "Default")
      (node (ref "C2") (pin "1") (pinfunction "1_1") (pintype "passive"))
      (node (ref "U1") (pin "3") (pinfunction "3V3OUT_3") (pintype "output"))
    )
    (net (code "55") (name "Net-(U1-CBUS0)") (class "Default")
      (node (ref "R5") (pin "2") (pinfunction "2_2") (pintype "passive"))
      (node (ref "U1") (pin "6") (pinfunction "CBUS0_6") (pintype "bidirectional"))
    )
    (net (code "56") (name "Net-(U1-RTS#)") (class "Default")
      (node (ref "C5") (pin "1") (pinfunction "1_1") (pintype "passive"))
      (node (ref "U1") (pin "8") (pinfunction "RTS#_8") (pintype "output"))
    )
    (net (code "57") (name "Net-(U1-RXD)") (class "Default")
      (node (ref "R27") (pin "1") (pinfunction "1_1") (pintype "passive"))
      (node (ref "U1") (pin "10") (pinfunction "RXD_10") (pintype "input"))
    )
    (net (code "58") (name "Net-(U1-TXD)") (class "Default")
      (node (ref "R28") (pin "1") (pinfunction "1_1") (pintype "passive"))
      (node (ref "U1") (pin "7") (pinfunction "TXD_7") (pintype "output"))
    )
    (net (code "59") (name "Net-(U1-USBDM)") (class "Default")
      (node (ref "R1") (pin "2") (pinfunction "2_2") (pintype "passive"))
      (node (ref "U1") (pin "1") (pinfunction "USBDM_1") (pintype "bidirectional"))
    )
    (net (code "60") (name "Net-(U1-USBDP)") (class "Default")
      (node (ref "R2") (pin "2") (pinfunction "2_2") (pintype "passive"))
      (node (ref "U1") (pin "12") (pinfunction "USBDP_12") (pintype "bidirectional"))
    )
    (net (code "61") (name "Net-(U1-~{RESET#})") (class "Default")
      (node (ref "R3") (pin "1") (pinfunction "1_1") (pintype "passive"))
      (node (ref "U1") (pin "2") (pinfunction "~{RESET#}_2") (pintype "input"))
    )
    (net (code "62") (name "Net-(U2-ILIM)") (class "Default")
      (node (ref "R12") (pin "1") (pinfunction "1_1") (pintype "passive"))
      (node (ref "U2") (pin "12") (pinfunction "ILIM_12") (pintype "input"))
    )
    (net (code "63") (name "Net-(U2-ISET)") (class "Default")
      (node (ref "R23") (pin "2") (pinfunction "2_2") (pintype "passive"))
      (node (ref "U2") (pin "16") (pinfunction "ISET_16") (pintype "bidirectional"))
    )
    (net (code "64") (name "Net-(U2-TS)") (class "Default")
      (node (ref "R10") (pin "1") (pinfunction "1_1") (pintype "passive"))
      (node (ref "U2") (pin "1") (pinfunction "TS_1") (pintype "input"))
    )
    (net (code "65") (name "Net-(U4-CPOUT)") (class "Default")
      (node (ref "C23") (pin "1") (pinfunction "1_1") (pintype "passive"))
      (node (ref "U4") (pin "20") (pinfunction "CPOUT_20") (pintype "passive"))
    )
    (net (code "66") (name "unconnected-(IC2-CLKO-Pad2)") (class "Default")
      (node (ref "IC2") (pin "2") (pinfunction "CLKO_2") (pintype "bidirectional"))
    )
    (net (code "67") (name "unconnected-(IC2-CLKOE-Pad4)") (class "Default")
      (node (ref "IC2") (pin "4") (pinfunction "CLKOE_4") (pintype "bidirectional"))
    )
    (net (code "68") (name "unconnected-(IC2-EVI-Pad7)") (class "Default")
      (node (ref "IC2") (pin "7") (pinfunction "EVI_7") (pintype "bidirectional"))
    )
    (net (code "69") (name "unconnected-(IC5-NC-Pad5)") (class "Default")
      (node (ref "IC5") (pin "5") (pinfunction "NC_5") (pintype "bidirectional"))
    )
    (net (code "70") (name "unconnected-(J2-CC1-PadA5)") (class "Default")
      (node (ref "J2") (pin "A5") (pinfunction "CC1_A5") (pintype "bidirectional"))
    )
    (net (code "71") (name "unconnected-(J2-CC2-PadB5)") (class "Default")
      (node (ref "J2") (pin "B5") (pinfunction "CC2_B5") (pintype "bidirectional"))
    )
    (net (code "72") (name "unconnected-(J2-SBU1-PadA8)") (class "Default")
      (node (ref "J2") (pin "A8") (pinfunction "SBU1_A8") (pintype "bidirectional"))
    )
    (net (code "73") (name "unconnected-(J2-SBU2-PadB8)") (class "Default")
      (node (ref "J2") (pin "B8") (pinfunction "SBU2_B8") (pintype "bidirectional"))
    )
    (net (code "74") (name "unconnected-(LCD1-PadM1)") (class "Default")
      (node (ref "LCD1") (pin "M1") (pinfunction "M1_M1") (pintype "bidirectional"))
    )
    (net (code "75") (name "unconnected-(LCD1-PadM2)") (class "Default")
      (node (ref "LCD1") (pin "M2") (pinfunction "M2_M2") (pintype "bidirectional"))
    )
    (net (code "76") (name "unconnected-(LCD1-REC-Pad11)") (class "Default")
      (node (ref "LCD1") (pin "11") (pinfunction "REC_11") (pintype "bidirectional"))
    )
    (net (code "77") (name "unconnected-(LCD1-RECO{slash}NC-Pad5)") (class "Default")
      (node (ref "LCD1") (pin "5") (pinfunction "RECO/NC_5") (pintype "bidirectional"))
    )
    (net (code "78") (name "unconnected-(LCD1-VHTEST_NC-Pad9)") (class "Default")
      (node (ref "LCD1") (pin "9") (pinfunction "VHTEST_NC_9") (pintype "bidirectional"))
    )
    (net (code "79") (name "unconnected-(LCD1-VHTEST_REF-Pad10)") (class "Default")
      (node (ref "LCD1") (pin "10") (pinfunction "VHTEST_REF_10") (pintype "bidirectional"))
    )
    (net (code "80") (name "unconnected-(U$1-DRDY-Pad8)") (class "Default")
      (node (ref "U$1") (pin "8") (pinfunction "DRDY_8") (pintype "bidirectional"))
    )
    (net (code "81") (name "unconnected-(U$1-INT-Pad7)") (class "Default")
      (node (ref "U$1") (pin "7") (pinfunction "INT_7") (pintype "bidirectional"))
    )
    (net (code "82") (name "unconnected-(U1-CTS#-Pad11)") (class "Default")
      (node (ref "U1") (pin "11") (pinfunction "CTS#_11") (pintype "input"))
    )
    (net (code "83") (name "unconnected-(U4-INT-Pad12)") (class "Default")
      (node (ref "U4") (pin "12") (pinfunction "INT_12") (pintype "output"))
    )
    (net (code "84") (name "unconnected-(U4-RESV-Pad19)") (class "Default")
      (node (ref "U4") (pin "19") (pinfunction "RESV_19") (pintype "passive"))
    )
    (net (code "85") (name "unconnected-(U4-RESV-Pad21)") (class "Default")
      (node (ref "U4") (pin "21") (pinfunction "RESV_21") (pintype "passive"))
    )
    (net (code "86") (name "unconnected-(U4-RESV-Pad22)") (class "Default")
      (node (ref "U4") (pin "22") (pinfunction "RESV_22") (pintype "passive"))
    )
  )
)
